# schematic.net
KiCad netlist of a schematic drawn in EAGLE
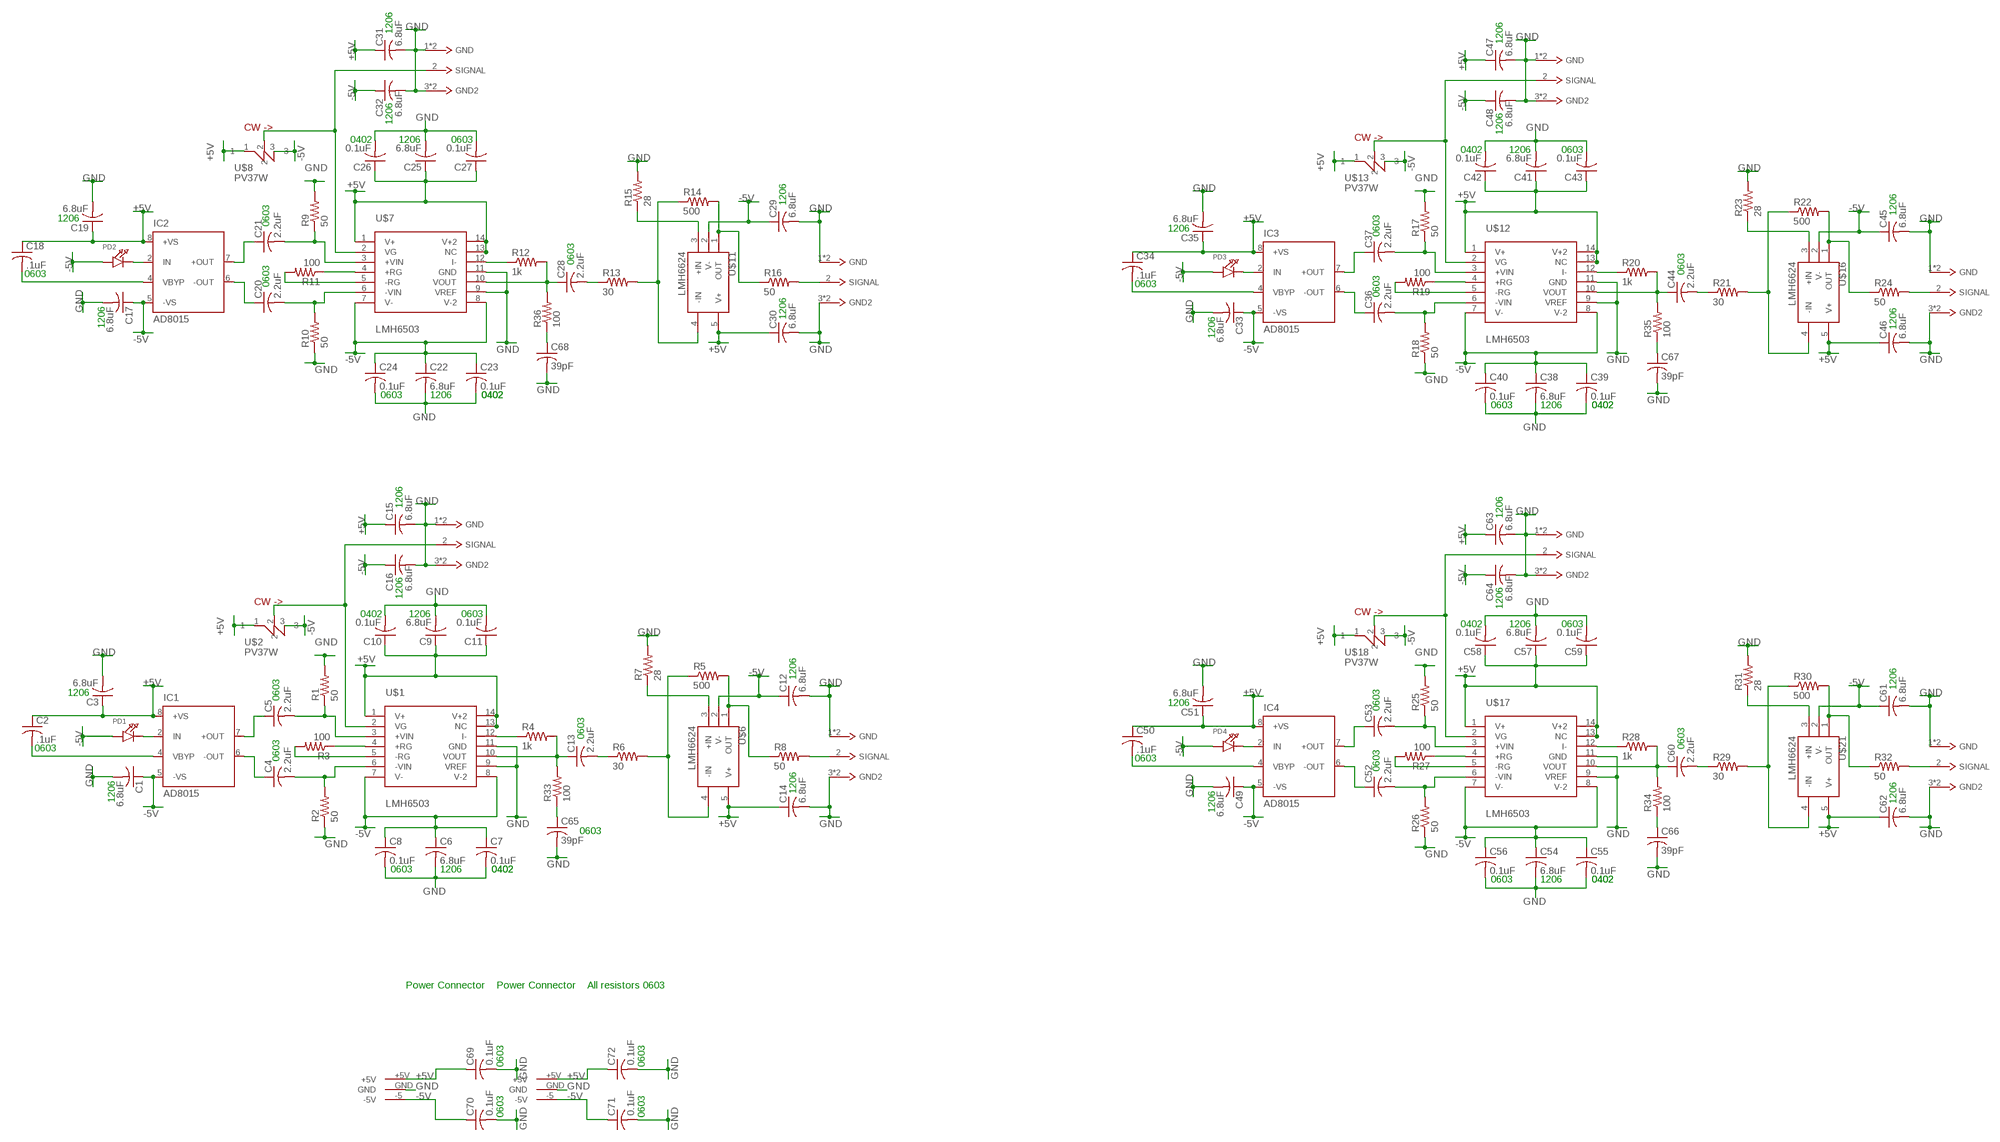
[diagram p0: schematic, sheet 1]

(export (version "E")
  (design (tool "Eeschema 10.0.6"))
  (components
    (comp (ref "C1")
      (value "6.8uF")
      (footprint "eagle-import:C1206")
      (libsource (lib "eagle-import") (part "C-USC1206"))
    )
    (comp (ref "C2")
      (value ".1uF")
      (footprint "eagle-import:C0603")
      (libsource (lib "eagle-import") (part "C-USC0603"))
    )
    (comp (ref "C3")
      (value "6.8uF")
      (footprint "eagle-import:C1206")
      (libsource (lib "eagle-import") (part "C-USC1206"))
    )
    (comp (ref "C4")
      (value "2.2uF")
      (footprint "eagle-import:C0603")
      (libsource (lib "eagle-import") (part "C-USC0603"))
    )
    (comp (ref "C5")
      (value "2.2uF")
      (footprint "eagle-import:C0603")
      (libsource (lib "eagle-import") (part "C-USC0603"))
    )
    (comp (ref "C6")
      (value "6.8uF")
      (footprint "eagle-import:C1206")
      (libsource (lib "eagle-import") (part "C-USC1206"))
    )
    (comp (ref "C7")
      (value "0.1uF")
      (footprint "eagle-import:C0402")
      (libsource (lib "eagle-import") (part "C-USC0402"))
    )
    (comp (ref "C8")
      (value "0.1uF")
      (footprint "eagle-import:C0603")
      (libsource (lib "eagle-import") (part "C-USC0603"))
    )
    (comp (ref "C9")
      (value "6.8uF")
      (footprint "eagle-import:C1206")
      (libsource (lib "eagle-import") (part "C-USC1206"))
    )
    (comp (ref "C10")
      (value "0.1uF")
      (footprint "eagle-import:C0402")
      (libsource (lib "eagle-import") (part "C-USC0402"))
    )
    (comp (ref "C11")
      (value "0.1uF")
      (footprint "eagle-import:C0603")
      (libsource (lib "eagle-import") (part "C-USC0603"))
    )
    (comp (ref "C12")
      (value "6.8uF")
      (footprint "eagle-import:C1206")
      (libsource (lib "eagle-import") (part "C-USC1206"))
    )
    (comp (ref "C13")
      (value "2.2uF")
      (footprint "eagle-import:C0603")
      (libsource (lib "eagle-import") (part "C-USC0603"))
    )
    (comp (ref "C14")
      (value "6.8uF")
      (footprint "eagle-import:C1206")
      (libsource (lib "eagle-import") (part "C-USC1206"))
    )
    (comp (ref "C15")
      (value "6.8uF")
      (footprint "eagle-import:C1206")
      (libsource (lib "eagle-import") (part "C-USC1206"))
    )
    (comp (ref "C16")
      (value "6.8uF")
      (footprint "eagle-import:C1206")
      (libsource (lib "eagle-import") (part "C-USC1206"))
    )
    (comp (ref "C17")
      (value "6.8uF")
      (footprint "eagle-import:C1206")
      (libsource (lib "eagle-import") (part "C-USC1206"))
    )
    (comp (ref "C18")
      (value ".1uF")
      (footprint "eagle-import:C0603")
      (libsource (lib "eagle-import") (part "C-USC0603"))
    )
    (comp (ref "C19")
      (value "6.8uF")
      (footprint "eagle-import:C1206")
      (libsource (lib "eagle-import") (part "C-USC1206"))
    )
    (comp (ref "C20")
      (value "2.2uF")
      (footprint "eagle-import:C0603")
      (libsource (lib "eagle-import") (part "C-USC0603"))
    )
    (comp (ref "C21")
      (value "2.2uF")
      (footprint "eagle-import:C0603")
      (libsource (lib "eagle-import") (part "C-USC0603"))
    )
    (comp (ref "C22")
      (value "6.8uF")
      (footprint "eagle-import:C1206")
      (libsource (lib "eagle-import") (part "C-USC1206"))
    )
    (comp (ref "C23")
      (value "0.1uF")
      (footprint "eagle-import:C0402")
      (libsource (lib "eagle-import") (part "C-USC0402"))
    )
    (comp (ref "C24")
      (value "0.1uF")
      (footprint "eagle-import:C0603")
      (libsource (lib "eagle-import") (part "C-USC0603"))
    )
    (comp (ref "C25")
      (value "6.8uF")
      (footprint "eagle-import:C1206")
      (libsource (lib "eagle-import") (part "C-USC1206"))
    )
    (comp (ref "C26")
      (value "0.1uF")
      (footprint "eagle-import:C0402")
      (libsource (lib "eagle-import") (part "C-USC0402"))
    )
    (comp (ref "C27")
      (value "0.1uF")
      (footprint "eagle-import:C0603")
      (libsource (lib "eagle-import") (part "C-USC0603"))
    )
    (comp (ref "C28")
      (value "2.2uF")
      (footprint "eagle-import:C0603")
      (libsource (lib "eagle-import") (part "C-USC0603"))
    )
    (comp (ref "C29")
      (value "6.8uF")
      (footprint "eagle-import:C1206")
      (libsource (lib "eagle-import") (part "C-USC1206"))
    )
    (comp (ref "C30")
      (value "6.8uF")
      (footprint "eagle-import:C1206")
      (libsource (lib "eagle-import") (part "C-USC1206"))
    )
    (comp (ref "C31")
      (value "6.8uF")
      (footprint "eagle-import:C1206")
      (libsource (lib "eagle-import") (part "C-USC1206"))
    )
    (comp (ref "C32")
      (value "6.8uF")
      (footprint "eagle-import:C1206")
      (libsource (lib "eagle-import") (part "C-USC1206"))
    )
    (comp (ref "C33")
      (value "6.8uF")
      (footprint "eagle-import:C1206")
      (libsource (lib "eagle-import") (part "C-USC1206"))
    )
    (comp (ref "C34")
      (value ".1uF")
      (footprint "eagle-import:C0603")
      (libsource (lib "eagle-import") (part "C-USC0603"))
    )
    (comp (ref "C35")
      (value "6.8uF")
      (footprint "eagle-import:C1206")
      (libsource (lib "eagle-import") (part "C-USC1206"))
    )
    (comp (ref "C36")
      (value "2.2uF")
      (footprint "eagle-import:C0603")
      (libsource (lib "eagle-import") (part "C-USC0603"))
    )
    (comp (ref "C37")
      (value "2.2uF")
      (footprint "eagle-import:C0603")
      (libsource (lib "eagle-import") (part "C-USC0603"))
    )
    (comp (ref "C38")
      (value "6.8uF")
      (footprint "eagle-import:C1206")
      (libsource (lib "eagle-import") (part "C-USC1206"))
    )
    (comp (ref "C39")
      (value "0.1uF")
      (footprint "eagle-import:C0402")
      (libsource (lib "eagle-import") (part "C-USC0402"))
    )
    (comp (ref "C40")
      (value "0.1uF")
      (footprint "eagle-import:C0603")
      (libsource (lib "eagle-import") (part "C-USC0603"))
    )
    (comp (ref "C41")
      (value "6.8uF")
      (footprint "eagle-import:C1206")
      (libsource (lib "eagle-import") (part "C-USC1206"))
    )
    (comp (ref "C42")
      (value "0.1uF")
      (footprint "eagle-import:C0402")
      (libsource (lib "eagle-import") (part "C-USC0402"))
    )
    (comp (ref "C43")
      (value "0.1uF")
      (footprint "eagle-import:C0603")
      (libsource (lib "eagle-import") (part "C-USC0603"))
    )
    (comp (ref "C44")
      (value "2.2uF")
      (footprint "eagle-import:C0603")
      (libsource (lib "eagle-import") (part "C-USC0603"))
    )
    (comp (ref "C45")
      (value "6.8uF")
      (footprint "eagle-import:C1206")
      (libsource (lib "eagle-import") (part "C-USC1206"))
    )
    (comp (ref "C46")
      (value "6.8uF")
      (footprint "eagle-import:C1206")
      (libsource (lib "eagle-import") (part "C-USC1206"))
    )
    (comp (ref "C47")
      (value "6.8uF")
      (footprint "eagle-import:C1206")
      (libsource (lib "eagle-import") (part "C-USC1206"))
    )
    (comp (ref "C48")
      (value "6.8uF")
      (footprint "eagle-import:C1206")
      (libsource (lib "eagle-import") (part "C-USC1206"))
    )
    (comp (ref "C49")
      (value "6.8uF")
      (footprint "eagle-import:C1206")
      (libsource (lib "eagle-import") (part "C-USC1206"))
    )
    (comp (ref "C50")
      (value ".1uF")
      (footprint "eagle-import:C0603")
      (libsource (lib "eagle-import") (part "C-USC0603"))
    )
    (comp (ref "C51")
      (value "6.8uF")
      (footprint "eagle-import:C1206")
      (libsource (lib "eagle-import") (part "C-USC1206"))
    )
    (comp (ref "C52")
      (value "2.2uF")
      (footprint "eagle-import:C0603")
      (libsource (lib "eagle-import") (part "C-USC0603"))
    )
    (comp (ref "C53")
      (value "2.2uF")
      (footprint "eagle-import:C0603")
      (libsource (lib "eagle-import") (part "C-USC0603"))
    )
    (comp (ref "C54")
      (value "6.8uF")
      (footprint "eagle-import:C1206")
      (libsource (lib "eagle-import") (part "C-USC1206"))
    )
    (comp (ref "C55")
      (value "0.1uF")
      (footprint "eagle-import:C0402")
      (libsource (lib "eagle-import") (part "C-USC0402"))
    )
    (comp (ref "C56")
      (value "0.1uF")
      (footprint "eagle-import:C0603")
      (libsource (lib "eagle-import") (part "C-USC0603"))
    )
    (comp (ref "C57")
      (value "6.8uF")
      (footprint "eagle-import:C1206")
      (libsource (lib "eagle-import") (part "C-USC1206"))
    )
    (comp (ref "C58")
      (value "0.1uF")
      (footprint "eagle-import:C0402")
      (libsource (lib "eagle-import") (part "C-USC0402"))
    )
    (comp (ref "C59")
      (value "0.1uF")
      (footprint "eagle-import:C0603")
      (libsource (lib "eagle-import") (part "C-USC0603"))
    )
    (comp (ref "C60")
      (value "2.2uF")
      (footprint "eagle-import:C0603")
      (libsource (lib "eagle-import") (part "C-USC0603"))
    )
    (comp (ref "C61")
      (value "6.8uF")
      (footprint "eagle-import:C1206")
      (libsource (lib "eagle-import") (part "C-USC1206"))
    )
    (comp (ref "C62")
      (value "6.8uF")
      (footprint "eagle-import:C1206")
      (libsource (lib "eagle-import") (part "C-USC1206"))
    )
    (comp (ref "C63")
      (value "6.8uF")
      (footprint "eagle-import:C1206")
      (libsource (lib "eagle-import") (part "C-USC1206"))
    )
    (comp (ref "C64")
      (value "6.8uF")
      (footprint "eagle-import:C1206")
      (libsource (lib "eagle-import") (part "C-USC1206"))
    )
    (comp (ref "C65")
      (value "39pF")
      (footprint "eagle-import:C0603")
      (libsource (lib "eagle-import") (part "C-USC0603"))
    )
    (comp (ref "C66")
      (value "39pF")
      (footprint "eagle-import:C0603")
      (libsource (lib "eagle-import") (part "C-USC0603"))
    )
    (comp (ref "C67")
      (value "39pF")
      (footprint "eagle-import:C0603")
      (libsource (lib "eagle-import") (part "C-USC0603"))
    )
    (comp (ref "C68")
      (value "39pF")
      (footprint "eagle-import:C0603")
      (libsource (lib "eagle-import") (part "C-USC0603"))
    )
    (comp (ref "C69")
      (value "0.1uF")
      (footprint "eagle-import:C0402")
      (libsource (lib "eagle-import") (part "C-USC0402"))
    )
    (comp (ref "C70")
      (value "0.1uF")
      (footprint "eagle-import:C0402")
      (libsource (lib "eagle-import") (part "C-USC0402"))
    )
    (comp (ref "C71")
      (value "0.1uF")
      (footprint "eagle-import:C0402")
      (libsource (lib "eagle-import") (part "C-USC0402"))
    )
    (comp (ref "C72")
      (value "0.1uF")
      (footprint "eagle-import:C0402")
      (libsource (lib "eagle-import") (part "C-USC0402"))
    )
    (comp (ref "IC1")
      (value "AD8015")
      (footprint "eagle-import:SO8")
      (fields (field (name "MPN") "AD8015ARZ"))
      (libsource (lib "eagle-import") (part "AD8015"))
    )
    (comp (ref "IC2")
      (value "AD8015")
      (footprint "eagle-import:SO8")
      (fields (field (name "MPN") "AD8015ARZ"))
      (libsource (lib "eagle-import") (part "AD8015"))
    )
    (comp (ref "IC3")
      (value "AD8015")
      (footprint "eagle-import:SO8")
      (fields (field (name "MPN") "AD8015ARZ"))
      (libsource (lib "eagle-import") (part "AD8015"))
    )
    (comp (ref "IC4")
      (value "AD8015")
      (footprint "eagle-import:SO8")
      (fields (field (name "MPN") "AD8015ARZ"))
      (libsource (lib "eagle-import") (part "AD8015"))
    )
    (comp (ref "PD1")
      (value "LED1206")
      (footprint "eagle-import:CHIPLED_1206")
      (libsource (lib "eagle-import") (part "LED1206"))
    )
    (comp (ref "PD2")
      (value "LED1206")
      (footprint "eagle-import:CHIPLED_1206")
      (libsource (lib "eagle-import") (part "LED1206"))
    )
    (comp (ref "PD3")
      (value "LED1206")
      (footprint "eagle-import:CHIPLED_1206")
      (libsource (lib "eagle-import") (part "LED1206"))
    )
    (comp (ref "PD4")
      (value "LED1206")
      (footprint "eagle-import:CHIPLED_1206")
      (libsource (lib "eagle-import") (part "LED1206"))
    )
    (comp (ref "R1")
      (value "50")
      (footprint "eagle-import:R0603")
      (libsource (lib "eagle-import") (part "R-US_R0603"))
    )
    (comp (ref "R2")
      (value "50")
      (footprint "eagle-import:R0603")
      (libsource (lib "eagle-import") (part "R-US_R0603"))
    )
    (comp (ref "R3")
      (value "100")
      (footprint "eagle-import:R0603")
      (libsource (lib "eagle-import") (part "R-US_R0603"))
    )
    (comp (ref "R4")
      (value "1k")
      (footprint "eagle-import:R0603")
      (libsource (lib "eagle-import") (part "R-US_R0603"))
    )
    (comp (ref "R5")
      (value "500")
      (footprint "eagle-import:R0603")
      (libsource (lib "eagle-import") (part "R-US_R0603"))
    )
    (comp (ref "R6")
      (value "30")
      (footprint "eagle-import:R0603")
      (libsource (lib "eagle-import") (part "R-US_R0603"))
    )
    (comp (ref "R7")
      (value "28")
      (footprint "eagle-import:R0603")
      (libsource (lib "eagle-import") (part "R-US_R0603"))
    )
    (comp (ref "R8")
      (value "50")
      (footprint "eagle-import:R0603")
      (libsource (lib "eagle-import") (part "R-US_R0603"))
    )
    (comp (ref "R9")
      (value "50")
      (footprint "eagle-import:R0603")
      (libsource (lib "eagle-import") (part "R-US_R0603"))
    )
    (comp (ref "R10")
      (value "50")
      (footprint "eagle-import:R0603")
      (libsource (lib "eagle-import") (part "R-US_R0603"))
    )
    (comp (ref "R11")
      (value "100")
      (footprint "eagle-import:R0603")
      (libsource (lib "eagle-import") (part "R-US_R0603"))
    )
    (comp (ref "R12")
      (value "1k")
      (footprint "eagle-import:R0603")
      (libsource (lib "eagle-import") (part "R-US_R0603"))
    )
    (comp (ref "R13")
      (value "30")
      (footprint "eagle-import:R0603")
      (libsource (lib "eagle-import") (part "R-US_R0603"))
    )
    (comp (ref "R14")
      (value "500")
      (footprint "eagle-import:R0603")
      (libsource (lib "eagle-import") (part "R-US_R0603"))
    )
    (comp (ref "R15")
      (value "28")
      (footprint "eagle-import:R0603")
      (libsource (lib "eagle-import") (part "R-US_R0603"))
    )
    (comp (ref "R16")
      (value "50")
      (footprint "eagle-import:R0603")
      (libsource (lib "eagle-import") (part "R-US_R0603"))
    )
    (comp (ref "R17")
      (value "50")
      (footprint "eagle-import:R0603")
      (libsource (lib "eagle-import") (part "R-US_R0603"))
    )
    (comp (ref "R18")
      (value "50")
      (footprint "eagle-import:R0603")
      (libsource (lib "eagle-import") (part "R-US_R0603"))
    )
    (comp (ref "R19")
      (value "100")
      (footprint "eagle-import:R0603")
      (libsource (lib "eagle-import") (part "R-US_R0603"))
    )
    (comp (ref "R20")
      (value "1k")
      (footprint "eagle-import:R0603")
      (libsource (lib "eagle-import") (part "R-US_R0603"))
    )
    (comp (ref "R21")
      (value "30")
      (footprint "eagle-import:R0603")
      (libsource (lib "eagle-import") (part "R-US_R0603"))
    )
    (comp (ref "R22")
      (value "500")
      (footprint "eagle-import:R0603")
      (libsource (lib "eagle-import") (part "R-US_R0603"))
    )
    (comp (ref "R23")
      (value "28")
      (footprint "eagle-import:R0603")
      (libsource (lib "eagle-import") (part "R-US_R0603"))
    )
    (comp (ref "R24")
      (value "50")
      (footprint "eagle-import:R0603")
      (libsource (lib "eagle-import") (part "R-US_R0603"))
    )
    (comp (ref "R25")
      (value "50")
      (footprint "eagle-import:R0603")
      (libsource (lib "eagle-import") (part "R-US_R0603"))
    )
    (comp (ref "R26")
      (value "50")
      (footprint "eagle-import:R0603")
      (libsource (lib "eagle-import") (part "R-US_R0603"))
    )
    (comp (ref "R27")
      (value "100")
      (footprint "eagle-import:R0603")
      (libsource (lib "eagle-import") (part "R-US_R0603"))
    )
    (comp (ref "R28")
      (value "1k")
      (footprint "eagle-import:R0603")
      (libsource (lib "eagle-import") (part "R-US_R0603"))
    )
    (comp (ref "R29")
      (value "30")
      (footprint "eagle-import:R0603")
      (libsource (lib "eagle-import") (part "R-US_R0603"))
    )
    (comp (ref "R30")
      (value "500")
      (footprint "eagle-import:R0603")
      (libsource (lib "eagle-import") (part "R-US_R0603"))
    )
    (comp (ref "R31")
      (value "28")
      (footprint "eagle-import:R0603")
      (libsource (lib "eagle-import") (part "R-US_R0603"))
    )
    (comp (ref "R32")
      (value "50")
      (footprint "eagle-import:R0603")
      (libsource (lib "eagle-import") (part "R-US_R0603"))
    )
    (comp (ref "R33")
      (value "100")
      (footprint "eagle-import:R0603")
      (libsource (lib "eagle-import") (part "R-US_R0603"))
    )
    (comp (ref "R34")
      (value "100")
      (footprint "eagle-import:R0603")
      (libsource (lib "eagle-import") (part "R-US_R0603"))
    )
    (comp (ref "R35")
      (value "100")
      (footprint "eagle-import:R0603")
      (libsource (lib "eagle-import") (part "R-US_R0603"))
    )
    (comp (ref "R36")
      (value "100")
      (footprint "eagle-import:R0603")
      (libsource (lib "eagle-import") (part "R-US_R0603"))
    )
    (comp (ref "U$1")
      (value "LMH6503")
      (footprint "eagle-import:SOIC14")
      (libsource (lib "eagle-import") (part "LMH6503"))
    )
    (comp (ref "U$2")
      (value "PV37W")
      (footprint "eagle-import:PV37W")
      (libsource (lib "eagle-import") (part "PV37W"))
    )
    (comp (ref "U$3")
      (value "DIVERSITYPWR")
      (footprint "eagle-import:DIVERSITYPOWER")
      (libsource (lib "eagle-import") (part "DIVERSITYPWR"))
    )
    (comp (ref "U$4")
      (value "BNCCONN")
      (footprint "eagle-import:BNCPADS")
      (libsource (lib "eagle-import") (part "BNCCONN"))
    )
    (comp (ref "U$5")
      (value "BNCCONN")
      (footprint "eagle-import:BNCPADS")
      (libsource (lib "eagle-import") (part "BNCCONN"))
    )
    (comp (ref "U$6")
      (value "LMH6624")
      (footprint "eagle-import:SOT-23")
      (libsource (lib "eagle-import") (part "LMH6624"))
    )
    (comp (ref "U$7")
      (value "LMH6503")
      (footprint "eagle-import:SOIC14")
      (libsource (lib "eagle-import") (part "LMH6503"))
    )
    (comp (ref "U$8")
      (value "PV37W")
      (footprint "eagle-import:PV37W")
      (libsource (lib "eagle-import") (part "PV37W"))
    )
    (comp (ref "U$9")
      (value "BNCCONN")
      (footprint "eagle-import:BNCPADS")
      (libsource (lib "eagle-import") (part "BNCCONN"))
    )
    (comp (ref "U$10")
      (value "BNCCONN")
      (footprint "eagle-import:BNCPADS")
      (libsource (lib "eagle-import") (part "BNCCONN"))
    )
    (comp (ref "U$11")
      (value "LMH6624")
      (footprint "eagle-import:SOT-23")
      (libsource (lib "eagle-import") (part "LMH6624"))
    )
    (comp (ref "U$12")
      (value "LMH6503")
      (footprint "eagle-import:SOIC14")
      (libsource (lib "eagle-import") (part "LMH6503"))
    )
    (comp (ref "U$13")
      (value "PV37W")
      (footprint "eagle-import:PV37W")
      (libsource (lib "eagle-import") (part "PV37W"))
    )
    (comp (ref "U$14")
      (value "BNCCONN")
      (footprint "eagle-import:BNCPADS")
      (libsource (lib "eagle-import") (part "BNCCONN"))
    )
    (comp (ref "U$15")
      (value "BNCCONN")
      (footprint "eagle-import:BNCPADS")
      (libsource (lib "eagle-import") (part "BNCCONN"))
    )
    (comp (ref "U$16")
      (value "LMH6624")
      (footprint "eagle-import:SOT-23")
      (libsource (lib "eagle-import") (part "LMH6624"))
    )
    (comp (ref "U$17")
      (value "LMH6503")
      (footprint "eagle-import:SOIC14")
      (libsource (lib "eagle-import") (part "LMH6503"))
    )
    (comp (ref "U$18")
      (value "PV37W")
      (footprint "eagle-import:PV37W")
      (libsource (lib "eagle-import") (part "PV37W"))
    )
    (comp (ref "U$19")
      (value "BNCCONN")
      (footprint "eagle-import:BNCPADS")
      (libsource (lib "eagle-import") (part "BNCCONN"))
    )
    (comp (ref "U$20")
      (value "BNCCONN")
      (footprint "eagle-import:BNCPADS")
      (libsource (lib "eagle-import") (part "BNCCONN"))
    )
    (comp (ref "U$21")
      (value "LMH6624")
      (footprint "eagle-import:SOT-23")
      (libsource (lib "eagle-import") (part "LMH6624"))
    )
    (comp (ref "U$22")
      (value "DIVERSITYPWR")
      (footprint "eagle-import:DIVERSITYPOWER")
      (libsource (lib "eagle-import") (part "DIVERSITYPWR"))
    )
  )
  (nets
    (net (code "1") (name "/+5V") (class "Default")
      (node (ref "C10") (pin "1") (pinfunction "1_1") (pintype "passive"))
      (node (ref "C11") (pin "1") (pinfunction "1_1") (pintype "passive"))
      (node (ref "C14") (pin "1") (pinfunction "1_1") (pintype "passive"))
      (node (ref "C15") (pin "1") (pinfunction "1_1") (pintype "passive"))
      (node (ref "C18") (pin "1") (pinfunction "1_1") (pintype "passive"))
      (node (ref "C19") (pin "1") (pinfunction "1_1") (pintype "passive"))
      (node (ref "C2") (pin "1") (pinfunction "1_1") (pintype "passive"))
      (node (ref "C25") (pin "1") (pinfunction "1_1") (pintype "passive"))
      (node (ref "C26") (pin "1") (pinfunction "1_1") (pintype "passive"))
      (node (ref "C27") (pin "1") (pinfunction "1_1") (pintype "passive"))
      (node (ref "C3") (pin "1") (pinfunction "1_1") (pintype "passive"))
      (node (ref "C30") (pin "1") (pinfunction "1_1") (pintype "passive"))
      (node (ref "C31") (pin "1") (pinfunction "1_1") (pintype "passive"))
      (node (ref "C34") (pin "1") (pinfunction "1_1") (pintype "passive"))
      (node (ref "C35") (pin "1") (pinfunction "1_1") (pintype "passive"))
      (node (ref "C41") (pin "1") (pinfunction "1_1") (pintype "passive"))
      (node (ref "C42") (pin "1") (pinfunction "1_1") (pintype "passive"))
      (node (ref "C43") (pin "1") (pinfunction "1_1") (pintype "passive"))
      (node (ref "C46") (pin "1") (pinfunction "1_1") (pintype "passive"))
      (node (ref "C47") (pin "1") (pinfunction "1_1") (pintype "passive"))
      (node (ref "C50") (pin "1") (pinfunction "1_1") (pintype "passive"))
      (node (ref "C51") (pin "1") (pinfunction "1_1") (pintype "passive"))
      (node (ref "C57") (pin "1") (pinfunction "1_1") (pintype "passive"))
      (node (ref "C58") (pin "1") (pinfunction "1_1") (pintype "passive"))
      (node (ref "C59") (pin "1") (pinfunction "1_1") (pintype "passive"))
      (node (ref "C62") (pin "1") (pinfunction "1_1") (pintype "passive"))
      (node (ref "C63") (pin "1") (pinfunction "1_1") (pintype "passive"))
      (node (ref "C69") (pin "1") (pinfunction "1_1") (pintype "passive"))
      (node (ref "C72") (pin "1") (pinfunction "1_1") (pintype "passive"))
      (node (ref "C9") (pin "1") (pinfunction "1_1") (pintype "passive"))
      (node (ref "IC1") (pin "8") (pinfunction "+VS_8") (pintype "input"))
      (node (ref "IC2") (pin "8") (pinfunction "+VS_8") (pintype "input"))
      (node (ref "IC3") (pin "8") (pinfunction "+VS_8") (pintype "input"))
      (node (ref "IC4") (pin "8") (pinfunction "+VS_8") (pintype "input"))
      (node (ref "U$1") (pin "1") (pinfunction "V+_1") (pintype "bidirectional"))
      (node (ref "U$1") (pin "13") (pinfunction "NC_13") (pintype "bidirectional"))
      (node (ref "U$1") (pin "14") (pinfunction "V+2_14") (pintype "bidirectional"))
      (node (ref "U$11") (pin "5") (pinfunction "V+_5") (pintype "bidirectional"))
      (node (ref "U$12") (pin "1") (pinfunction "V+_1") (pintype "bidirectional"))
      (node (ref "U$12") (pin "13") (pinfunction "NC_13") (pintype "bidirectional"))
      (node (ref "U$12") (pin "14") (pinfunction "V+2_14") (pintype "bidirectional"))
      (node (ref "U$13") (pin "1") (pinfunction "1_1") (pintype "bidirectional"))
      (node (ref "U$16") (pin "5") (pinfunction "V+_5") (pintype "bidirectional"))
      (node (ref "U$17") (pin "1") (pinfunction "V+_1") (pintype "bidirectional"))
      (node (ref "U$17") (pin "13") (pinfunction "NC_13") (pintype "bidirectional"))
      (node (ref "U$17") (pin "14") (pinfunction "V+2_14") (pintype "bidirectional"))
      (node (ref "U$18") (pin "1") (pinfunction "1_1") (pintype "bidirectional"))
      (node (ref "U$2") (pin "1") (pinfunction "1_1") (pintype "bidirectional"))
      (node (ref "U$21") (pin "5") (pinfunction "V+_5") (pintype "bidirectional"))
      (node (ref "U$22") (pin "+5V") (pinfunction "+5V_+5V") (pintype "bidirectional"))
      (node (ref "U$3") (pin "+5V") (pinfunction "+5V_+5V") (pintype "bidirectional"))
      (node (ref "U$6") (pin "5") (pinfunction "V+_5") (pintype "bidirectional"))
      (node (ref "U$7") (pin "1") (pinfunction "V+_1") (pintype "bidirectional"))
      (node (ref "U$7") (pin "13") (pinfunction "NC_13") (pintype "bidirectional"))
      (node (ref "U$7") (pin "14") (pinfunction "V+2_14") (pintype "bidirectional"))
      (node (ref "U$8") (pin "1") (pinfunction "1_1") (pintype "bidirectional"))
    )
    (net (code "2") (name "/-5V") (class "Default")
      (node (ref "C1") (pin "1") (pinfunction "1_1") (pintype "passive"))
      (node (ref "C12") (pin "1") (pinfunction "1_1") (pintype "passive"))
      (node (ref "C16") (pin "1") (pinfunction "1_1") (pintype "passive"))
      (node (ref "C17") (pin "1") (pinfunction "1_1") (pintype "passive"))
      (node (ref "C22") (pin "1") (pinfunction "1_1") (pintype "passive"))
      (node (ref "C23") (pin "1") (pinfunction "1_1") (pintype "passive"))
      (node (ref "C24") (pin "1") (pinfunction "1_1") (pintype "passive"))
      (node (ref "C29") (pin "1") (pinfunction "1_1") (pintype "passive"))
      (node (ref "C32") (pin "1") (pinfunction "1_1") (pintype "passive"))
      (node (ref "C33") (pin "1") (pinfunction "1_1") (pintype "passive"))
      (node (ref "C38") (pin "1") (pinfunction "1_1") (pintype "passive"))
      (node (ref "C39") (pin "1") (pinfunction "1_1") (pintype "passive"))
      (node (ref "C40") (pin "1") (pinfunction "1_1") (pintype "passive"))
      (node (ref "C45") (pin "1") (pinfunction "1_1") (pintype "passive"))
      (node (ref "C48") (pin "1") (pinfunction "1_1") (pintype "passive"))
      (node (ref "C49") (pin "1") (pinfunction "1_1") (pintype "passive"))
      (node (ref "C54") (pin "1") (pinfunction "1_1") (pintype "passive"))
      (node (ref "C55") (pin "1") (pinfunction "1_1") (pintype "passive"))
      (node (ref "C56") (pin "1") (pinfunction "1_1") (pintype "passive"))
      (node (ref "C6") (pin "1") (pinfunction "1_1") (pintype "passive"))
      (node (ref "C61") (pin "1") (pinfunction "1_1") (pintype "passive"))
      (node (ref "C64") (pin "1") (pinfunction "1_1") (pintype "passive"))
      (node (ref "C7") (pin "1") (pinfunction "1_1") (pintype "passive"))
      (node (ref "C70") (pin "1") (pinfunction "1_1") (pintype "passive"))
      (node (ref "C71") (pin "1") (pinfunction "1_1") (pintype "passive"))
      (node (ref "C8") (pin "1") (pinfunction "1_1") (pintype "passive"))
      (node (ref "IC1") (pin "5") (pinfunction "-VS_5") (pintype "input"))
      (node (ref "IC2") (pin "5") (pinfunction "-VS_5") (pintype "input"))
      (node (ref "IC3") (pin "5") (pinfunction "-VS_5") (pintype "input"))
      (node (ref "IC4") (pin "5") (pinfunction "-VS_5") (pintype "input"))
      (node (ref "PD1") (pin "A") (pinfunction "A_A") (pintype "passive"))
      (node (ref "PD2") (pin "A") (pinfunction "A_A") (pintype "passive"))
      (node (ref "PD3") (pin "A") (pinfunction "A_A") (pintype "passive"))
      (node (ref "PD4") (pin "A") (pinfunction "A_A") (pintype "passive"))
      (node (ref "U$1") (pin "7") (pinfunction "V-_7") (pintype "bidirectional"))
      (node (ref "U$1") (pin "8") (pinfunction "V-2_8") (pintype "bidirectional"))
      (node (ref "U$11") (pin "2") (pinfunction "V-_2") (pintype "bidirectional"))
      (node (ref "U$12") (pin "7") (pinfunction "V-_7") (pintype "bidirectional"))
      (node (ref "U$12") (pin "8") (pinfunction "V-2_8") (pintype "bidirectional"))
      (node (ref "U$13") (pin "3") (pinfunction "3_3") (pintype "bidirectional"))
      (node (ref "U$16") (pin "2") (pinfunction "V-_2") (pintype "bidirectional"))
      (node (ref "U$17") (pin "7") (pinfunction "V-_7") (pintype "bidirectional"))
      (node (ref "U$17") (pin "8") (pinfunction "V-2_8") (pintype "bidirectional"))
      (node (ref "U$18") (pin "3") (pinfunction "3_3") (pintype "bidirectional"))
      (node (ref "U$2") (pin "3") (pinfunction "3_3") (pintype "bidirectional"))
      (node (ref "U$21") (pin "2") (pinfunction "V-_2") (pintype "bidirectional"))
      (node (ref "U$22") (pin "-5") (pinfunction "-5V_-5") (pintype "bidirectional"))
      (node (ref "U$3") (pin "-5") (pinfunction "-5V_-5") (pintype "bidirectional"))
      (node (ref "U$6") (pin "2") (pinfunction "V-_2") (pintype "bidirectional"))
      (node (ref "U$7") (pin "7") (pinfunction "V-_7") (pintype "bidirectional"))
      (node (ref "U$7") (pin "8") (pinfunction "V-2_8") (pintype "bidirectional"))
      (node (ref "U$8") (pin "3") (pinfunction "3_3") (pintype "bidirectional"))
    )
    (net (code "3") (name "/GND") (class "Default")
      (node (ref "C1") (pin "2") (pinfunction "2_2") (pintype "passive"))
      (node (ref "C10") (pin "2") (pinfunction "2_2") (pintype "passive"))
      (node (ref "C11") (pin "2") (pinfunction "2_2") (pintype "passive"))
      (node (ref "C12") (pin "2") (pinfunction "2_2") (pintype "passive"))
      (node (ref "C14") (pin "2") (pinfunction "2_2") (pintype "passive"))
      (node (ref "C15") (pin "2") (pinfunction "2_2") (pintype "passive"))
      (node (ref "C16") (pin "2") (pinfunction "2_2") (pintype "passive"))
      (node (ref "C17") (pin "2") (pinfunction "2_2") (pintype "passive"))
      (node (ref "C19") (pin "2") (pinfunction "2_2") (pintype "passive"))
      (node (ref "C22") (pin "2") (pinfunction "2_2") (pintype "passive"))
      (node (ref "C23") (pin "2") (pinfunction "2_2") (pintype "passive"))
      (node (ref "C24") (pin "2") (pinfunction "2_2") (pintype "passive"))
      (node (ref "C25") (pin "2") (pinfunction "2_2") (pintype "passive"))
      (node (ref "C26") (pin "2") (pinfunction "2_2") (pintype "passive"))
      (node (ref "C27") (pin "2") (pinfunction "2_2") (pintype "passive"))
      (node (ref "C29") (pin "2") (pinfunction "2_2") (pintype "passive"))
      (node (ref "C3") (pin "2") (pinfunction "2_2") (pintype "passive"))
      (node (ref "C30") (pin "2") (pinfunction "2_2") (pintype "passive"))
      (node (ref "C31") (pin "2") (pinfunction "2_2") (pintype "passive"))
      (node (ref "C32") (pin "2") (pinfunction "2_2") (pintype "passive"))
      (node (ref "C33") (pin "2") (pinfunction "2_2") (pintype "passive"))
      (node (ref "C35") (pin "2") (pinfunction "2_2") (pintype "passive"))
      (node (ref "C38") (pin "2") (pinfunction "2_2") (pintype "passive"))
      (node (ref "C39") (pin "2") (pinfunction "2_2") (pintype "passive"))
      (node (ref "C40") (pin "2") (pinfunction "2_2") (pintype "passive"))
      (node (ref "C41") (pin "2") (pinfunction "2_2") (pintype "passive"))
      (node (ref "C42") (pin "2") (pinfunction "2_2") (pintype "passive"))
      (node (ref "C43") (pin "2") (pinfunction "2_2") (pintype "passive"))
      (node (ref "C45") (pin "2") (pinfunction "2_2") (pintype "passive"))
      (node (ref "C46") (pin "2") (pinfunction "2_2") (pintype "passive"))
      (node (ref "C47") (pin "2") (pinfunction "2_2") (pintype "passive"))
      (node (ref "C48") (pin "2") (pinfunction "2_2") (pintype "passive"))
      (node (ref "C49") (pin "2") (pinfunction "2_2") (pintype "passive"))
      (node (ref "C51") (pin "2") (pinfunction "2_2") (pintype "passive"))
      (node (ref "C54") (pin "2") (pinfunction "2_2") (pintype "passive"))
      (node (ref "C55") (pin "2") (pinfunction "2_2") (pintype "passive"))
      (node (ref "C56") (pin "2") (pinfunction "2_2") (pintype "passive"))
      (node (ref "C57") (pin "2") (pinfunction "2_2") (pintype "passive"))
      (node (ref "C58") (pin "2") (pinfunction "2_2") (pintype "passive"))
      (node (ref "C59") (pin "2") (pinfunction "2_2") (pintype "passive"))
      (node (ref "C6") (pin "2") (pinfunction "2_2") (pintype "passive"))
      (node (ref "C61") (pin "2") (pinfunction "2_2") (pintype "passive"))
      (node (ref "C62") (pin "2") (pinfunction "2_2") (pintype "passive"))
      (node (ref "C63") (pin "2") (pinfunction "2_2") (pintype "passive"))
      (node (ref "C64") (pin "2") (pinfunction "2_2") (pintype "passive"))
      (node (ref "C65") (pin "2") (pinfunction "2_2") (pintype "passive"))
      (node (ref "C66") (pin "2") (pinfunction "2_2") (pintype "passive"))
      (node (ref "C67") (pin "2") (pinfunction "2_2") (pintype "passive"))
      (node (ref "C68") (pin "2") (pinfunction "2_2") (pintype "passive"))
      (node (ref "C69") (pin "2") (pinfunction "2_2") (pintype "passive"))
      (node (ref "C7") (pin "2") (pinfunction "2_2") (pintype "passive"))
      (node (ref "C70") (pin "2") (pinfunction "2_2") (pintype "passive"))
      (node (ref "C71") (pin "2") (pinfunction "2_2") (pintype "passive"))
      (node (ref "C72") (pin "2") (pinfunction "2_2") (pintype "passive"))
      (node (ref "C8") (pin "2") (pinfunction "2_2") (pintype "passive"))
      (node (ref "C9") (pin "2") (pinfunction "2_2") (pintype "passive"))
      (node (ref "R1") (pin "2") (pinfunction "2_2") (pintype "passive"))
      (node (ref "R10") (pin "1") (pinfunction "1_1") (pintype "passive"))
      (node (ref "R15") (pin "2") (pinfunction "2_2") (pintype "passive"))
      (node (ref "R17") (pin "2") (pinfunction "2_2") (pintype "passive"))
      (node (ref "R18") (pin "1") (pinfunction "1_1") (pintype "passive"))
      (node (ref "R2") (pin "1") (pinfunction "1_1") (pintype "passive"))
      (node (ref "R23") (pin "2") (pinfunction "2_2") (pintype "passive"))
      (node (ref "R25") (pin "2") (pinfunction "2_2") (pintype "passive"))
      (node (ref "R26") (pin "1") (pinfunction "1_1") (pintype "passive"))
      (node (ref "R31") (pin "2") (pinfunction "2_2") (pintype "passive"))
      (node (ref "R7") (pin "2") (pinfunction "2_2") (pintype "passive"))
      (node (ref "R9") (pin "2") (pinfunction "2_2") (pintype "passive"))
      (node (ref "U$1") (pin "11") (pinfunction "GND_11") (pintype "bidirectional"))
      (node (ref "U$1") (pin "9") (pinfunction "VREF_9") (pintype "bidirectional"))
      (node (ref "U$10") (pin "1") (pinfunction "GND_1") (pintype "bidirectional"))
      (node (ref "U$10") (pin "3") (pinfunction "GND2_3") (pintype "bidirectional"))
      (node (ref "U$10") (pin "4") (pinfunction "GND_4") (pintype "bidirectional"))
      (node (ref "U$10") (pin "5") (pinfunction "GND2_5") (pintype "bidirectional"))
      (node (ref "U$12") (pin "11") (pinfunction "GND_11") (pintype "bidirectional"))
      (node (ref "U$12") (pin "9") (pinfunction "VREF_9") (pintype "bidirectional"))
      (node (ref "U$14") (pin "1") (pinfunction "GND_1") (pintype "bidirectional"))
      (node (ref "U$14") (pin "3") (pinfunction "GND2_3") (pintype "bidirectional"))
      (node (ref "U$14") (pin "4") (pinfunction "GND_4") (pintype "bidirectional"))
      (node (ref "U$14") (pin "5") (pinfunction "GND2_5") (pintype "bidirectional"))
      (node (ref "U$15") (pin "1") (pinfunction "GND_1") (pintype "bidirectional"))
      (node (ref "U$15") (pin "3") (pinfunction "GND2_3") (pintype "bidirectional"))
      (node (ref "U$15") (pin "4") (pinfunction "GND_4") (pintype "bidirectional"))
      (node (ref "U$15") (pin "5") (pinfunction "GND2_5") (pintype "bidirectional"))
      (node (ref "U$17") (pin "11") (pinfunction "GND_11") (pintype "bidirectional"))
      (node (ref "U$17") (pin "9") (pinfunction "VREF_9") (pintype "bidirectional"))
      (node (ref "U$19") (pin "1") (pinfunction "GND_1") (pintype "bidirectional"))
      (node (ref "U$19") (pin "3") (pinfunction "GND2_3") (pintype "bidirectional"))
      (node (ref "U$19") (pin "4") (pinfunction "GND_4") (pintype "bidirectional"))
      (node (ref "U$19") (pin "5") (pinfunction "GND2_5") (pintype "bidirectional"))
      (node (ref "U$20") (pin "1") (pinfunction "GND_1") (pintype "bidirectional"))
      (node (ref "U$20") (pin "3") (pinfunction "GND2_3") (pintype "bidirectional"))
      (node (ref "U$20") (pin "4") (pinfunction "GND_4") (pintype "bidirectional"))
      (node (ref "U$20") (pin "5") (pinfunction "GND2_5") (pintype "bidirectional"))
      (node (ref "U$22") (pin "GND") (pinfunction "GND_GND") (pintype "bidirectional"))
      (node (ref "U$3") (pin "GND") (pinfunction "GND_GND") (pintype "bidirectional"))
      (node (ref "U$4") (pin "1") (pinfunction "GND_1") (pintype "bidirectional"))
      (node (ref "U$4") (pin "3") (pinfunction "GND2_3") (pintype "bidirectional"))
      (node (ref "U$4") (pin "4") (pinfunction "GND_4") (pintype "bidirectional"))
      (node (ref "U$4") (pin "5") (pinfunction "GND2_5") (pintype "bidirectional"))
      (node (ref "U$5") (pin "1") (pinfunction "GND_1") (pintype "bidirectional"))
      (node (ref "U$5") (pin "3") (pinfunction "GND2_3") (pintype "bidirectional"))
      (node (ref "U$5") (pin "4") (pinfunction "GND_4") (pintype "bidirectional"))
      (node (ref "U$5") (pin "5") (pinfunction "GND2_5") (pintype "bidirectional"))
      (node (ref "U$7") (pin "11") (pinfunction "GND_11") (pintype "bidirectional"))
      (node (ref "U$7") (pin "9") (pinfunction "VREF_9") (pintype "bidirectional"))
      (node (ref "U$9") (pin "1") (pinfunction "GND_1") (pintype "bidirectional"))
      (node (ref "U$9") (pin "3") (pinfunction "GND2_3") (pintype "bidirectional"))
      (node (ref "U$9") (pin "4") (pinfunction "GND_4") (pintype "bidirectional"))
      (node (ref "U$9") (pin "5") (pinfunction "GND2_5") (pintype "bidirectional"))
    )
    (net (code "4") (name "Net-(C13-Pad2)") (class "Default")
      (node (ref "C13") (pin "2") (pinfunction "2_2") (pintype "passive"))
      (node (ref "R6") (pin "1") (pinfunction "1_1") (pintype "passive"))
    )
    (net (code "5") (name "Net-(C28-Pad2)") (class "Default")
      (node (ref "C28") (pin "2") (pinfunction "2_2") (pintype "passive"))
      (node (ref "R13") (pin "1") (pinfunction "1_1") (pintype "passive"))
    )
    (net (code "6") (name "Net-(C44-Pad2)") (class "Default")
      (node (ref "C44") (pin "2") (pinfunction "2_2") (pintype "passive"))
      (node (ref "R21") (pin "1") (pinfunction "1_1") (pintype "passive"))
    )
    (net (code "7") (name "Net-(C60-Pad2)") (class "Default")
      (node (ref "C60") (pin "2") (pinfunction "2_2") (pintype "passive"))
      (node (ref "R29") (pin "1") (pinfunction "1_1") (pintype "passive"))
    )
    (net (code "8") (name "Net-(C65-Pad1)") (class "Default")
      (node (ref "C65") (pin "1") (pinfunction "1_1") (pintype "passive"))
      (node (ref "R33") (pin "1") (pinfunction "1_1") (pintype "passive"))
    )
    (net (code "9") (name "Net-(C66-Pad1)") (class "Default")
      (node (ref "C66") (pin "1") (pinfunction "1_1") (pintype "passive"))
      (node (ref "R34") (pin "1") (pinfunction "1_1") (pintype "passive"))
    )
    (net (code "10") (name "Net-(C67-Pad1)") (class "Default")
      (node (ref "C67") (pin "1") (pinfunction "1_1") (pintype "passive"))
      (node (ref "R35") (pin "1") (pinfunction "1_1") (pintype "passive"))
    )
    (net (code "11") (name "Net-(C68-Pad1)") (class "Default")
      (node (ref "C68") (pin "1") (pinfunction "1_1") (pintype "passive"))
      (node (ref "R36") (pin "1") (pinfunction "1_1") (pintype "passive"))
    )
    (net (code "12") (name "Net-(IC1-+OUT)") (class "Default")
      (node (ref "C5") (pin "1") (pinfunction "1_1") (pintype "passive"))
      (node (ref "IC1") (pin "7") (pinfunction "+OUT_7") (pintype "output"))
    )
    (net (code "13") (name "Net-(IC1--OUT)") (class "Default")
      (node (ref "C4") (pin "1") (pinfunction "1_1") (pintype "passive"))
      (node (ref "IC1") (pin "6") (pinfunction "-OUT_6") (pintype "output"))
    )
    (net (code "14") (name "Net-(IC1-IN)") (class "Default")
      (node (ref "IC1") (pin "2") (pinfunction "IN_2") (pintype "input"))
      (node (ref "PD1") (pin "C") (pinfunction "C_C") (pintype "passive"))
    )
    (net (code "15") (name "Net-(IC1-VBYP)") (class "Default")
      (node (ref "C2") (pin "2") (pinfunction "2_2") (pintype "passive"))
      (node (ref "IC1") (pin "4") (pinfunction "VBYP_4") (pintype "input"))
    )
    (net (code "16") (name "Net-(IC2-+OUT)") (class "Default")
      (node (ref "C21") (pin "1") (pinfunction "1_1") (pintype "passive"))
      (node (ref "IC2") (pin "7") (pinfunction "+OUT_7") (pintype "output"))
    )
    (net (code "17") (name "Net-(IC2--OUT)") (class "Default")
      (node (ref "C20") (pin "1") (pinfunction "1_1") (pintype "passive"))
      (node (ref "IC2") (pin "6") (pinfunction "-OUT_6") (pintype "output"))
    )
    (net (code "18") (name "Net-(IC2-IN)") (class "Default")
      (node (ref "IC2") (pin "2") (pinfunction "IN_2") (pintype "input"))
      (node (ref "PD2") (pin "C") (pinfunction "C_C") (pintype "passive"))
    )
    (net (code "19") (name "Net-(IC2-VBYP)") (class "Default")
      (node (ref "C18") (pin "2") (pinfunction "2_2") (pintype "passive"))
      (node (ref "IC2") (pin "4") (pinfunction "VBYP_4") (pintype "input"))
    )
    (net (code "20") (name "Net-(IC3-+OUT)") (class "Default")
      (node (ref "C37") (pin "1") (pinfunction "1_1") (pintype "passive"))
      (node (ref "IC3") (pin "7") (pinfunction "+OUT_7") (pintype "output"))
    )
    (net (code "21") (name "Net-(IC3--OUT)") (class "Default")
      (node (ref "C36") (pin "1") (pinfunction "1_1") (pintype "passive"))
      (node (ref "IC3") (pin "6") (pinfunction "-OUT_6") (pintype "output"))
    )
    (net (code "22") (name "Net-(IC3-IN)") (class "Default")
      (node (ref "IC3") (pin "2") (pinfunction "IN_2") (pintype "input"))
      (node (ref "PD3") (pin "C") (pinfunction "C_C") (pintype "passive"))
    )
    (net (code "23") (name "Net-(IC3-VBYP)") (class "Default")
      (node (ref "C34") (pin "2") (pinfunction "2_2") (pintype "passive"))
      (node (ref "IC3") (pin "4") (pinfunction "VBYP_4") (pintype "input"))
    )
    (net (code "24") (name "Net-(IC4-+OUT)") (class "Default")
      (node (ref "C53") (pin "1") (pinfunction "1_1") (pintype "passive"))
      (node (ref "IC4") (pin "7") (pinfunction "+OUT_7") (pintype "output"))
    )
    (net (code "25") (name "Net-(IC4--OUT)") (class "Default")
      (node (ref "C52") (pin "1") (pinfunction "1_1") (pintype "passive"))
      (node (ref "IC4") (pin "6") (pinfunction "-OUT_6") (pintype "output"))
    )
    (net (code "26") (name "Net-(IC4-IN)") (class "Default")
      (node (ref "IC4") (pin "2") (pinfunction "IN_2") (pintype "input"))
      (node (ref "PD4") (pin "C") (pinfunction "C_C") (pintype "passive"))
    )
    (net (code "27") (name "Net-(IC4-VBYP)") (class "Default")
      (node (ref "C50") (pin "2") (pinfunction "2_2") (pintype "passive"))
      (node (ref "IC4") (pin "4") (pinfunction "VBYP_4") (pintype "input"))
    )
    (net (code "28") (name "Net-(U$1-+RG)") (class "Default")
      (node (ref "R3") (pin "1") (pinfunction "1_1") (pintype "passive"))
      (node (ref "U$1") (pin "4") (pinfunction "+RG_4") (pintype "bidirectional"))
    )
    (net (code "29") (name "Net-(U$1-+VIN)") (class "Default")
      (node (ref "C5") (pin "2") (pinfunction "2_2") (pintype "passive"))
      (node (ref "R1") (pin "1") (pinfunction "1_1") (pintype "passive"))
      (node (ref "U$1") (pin "3") (pinfunction "+VIN_3") (pintype "bidirectional"))
    )
    (net (code "30") (name "Net-(U$1--RG)") (class "Default")
      (node (ref "R3") (pin "2") (pinfunction "2_2") (pintype "passive"))
      (node (ref "U$1") (pin "5") (pinfunction "-RG_5") (pintype "bidirectional"))
    )
    (net (code "31") (name "Net-(U$1--VIN)") (class "Default")
      (node (ref "C4") (pin "2") (pinfunction "2_2") (pintype "passive"))
      (node (ref "R2") (pin "2") (pinfunction "2_2") (pintype "passive"))
      (node (ref "U$1") (pin "6") (pinfunction "-VIN_6") (pintype "bidirectional"))
    )
    (net (code "32") (name "Net-(U$1-I-)") (class "Default")
      (node (ref "R4") (pin "1") (pinfunction "1_1") (pintype "passive"))
      (node (ref "U$1") (pin "12") (pinfunction "I-_12") (pintype "bidirectional"))
    )
    (net (code "33") (name "Net-(U$1-VG)") (class "Default")
      (node (ref "U$1") (pin "2") (pinfunction "VG_2") (pintype "bidirectional"))
      (node (ref "U$2") (pin "2") (pinfunction "2_2") (pintype "bidirectional"))
      (node (ref "U$4") (pin "2") (pinfunction "SIGNAL_2") (pintype "bidirectional"))
    )
    (net (code "34") (name "Net-(U$1-VOUT)") (class "Default")
      (node (ref "C13") (pin "1") (pinfunction "1_1") (pintype "passive"))
      (node (ref "R33") (pin "2") (pinfunction "2_2") (pintype "passive"))
      (node (ref "R4") (pin "2") (pinfunction "2_2") (pintype "passive"))
      (node (ref "U$1") (pin "10") (pinfunction "VOUT_10") (pintype "bidirectional"))
    )
    (net (code "35") (name "Net-(U$5-SIGNAL)") (class "Default")
      (node (ref "R8") (pin "2") (pinfunction "2_2") (pintype "passive"))
      (node (ref "U$5") (pin "2") (pinfunction "SIGNAL_2") (pintype "bidirectional"))
    )
    (net (code "36") (name "Net-(U$6-+IN)") (class "Default")
      (node (ref "R7") (pin "1") (pinfunction "1_1") (pintype "passive"))
      (node (ref "U$6") (pin "3") (pinfunction "+IN_3") (pintype "bidirectional"))
    )
    (net (code "37") (name "Net-(U$6--IN)") (class "Default")
      (node (ref "R5") (pin "1") (pinfunction "1_1") (pintype "passive"))
      (node (ref "R6") (pin "2") (pinfunction "2_2") (pintype "passive"))
      (node (ref "U$6") (pin "4") (pinfunction "-IN_4") (pintype "bidirectional"))
    )
    (net (code "38") (name "Net-(U$6-OUT)") (class "Default")
      (node (ref "R5") (pin "2") (pinfunction "2_2") (pintype "passive"))
      (node (ref "R8") (pin "1") (pinfunction "1_1") (pintype "passive"))
      (node (ref "U$6") (pin "1") (pinfunction "OUT_1") (pintype "bidirectional"))
    )
    (net (code "39") (name "Net-(U$7-+RG)") (class "Default")
      (node (ref "R11") (pin "1") (pinfunction "1_1") (pintype "passive"))
      (node (ref "U$7") (pin "4") (pinfunction "+RG_4") (pintype "bidirectional"))
    )
    (net (code "40") (name "Net-(U$7-+VIN)") (class "Default")
      (node (ref "C21") (pin "2") (pinfunction "2_2") (pintype "passive"))
      (node (ref "R9") (pin "1") (pinfunction "1_1") (pintype "passive"))
      (node (ref "U$7") (pin "3") (pinfunction "+VIN_3") (pintype "bidirectional"))
    )
    (net (code "41") (name "Net-(U$7--RG)") (class "Default")
      (node (ref "R11") (pin "2") (pinfunction "2_2") (pintype "passive"))
      (node (ref "U$7") (pin "5") (pinfunction "-RG_5") (pintype "bidirectional"))
    )
    (net (code "42") (name "Net-(U$7--VIN)") (class "Default")
      (node (ref "C20") (pin "2") (pinfunction "2_2") (pintype "passive"))
      (node (ref "R10") (pin "2") (pinfunction "2_2") (pintype "passive"))
      (node (ref "U$7") (pin "6") (pinfunction "-VIN_6") (pintype "bidirectional"))
    )
    (net (code "43") (name "Net-(U$7-I-)") (class "Default")
      (node (ref "R12") (pin "1") (pinfunction "1_1") (pintype "passive"))
      (node (ref "U$7") (pin "12") (pinfunction "I-_12") (pintype "bidirectional"))
    )
    (net (code "44") (name "Net-(U$7-VG)") (class "Default")
      (node (ref "U$7") (pin "2") (pinfunction "VG_2") (pintype "bidirectional"))
      (node (ref "U$8") (pin "2") (pinfunction "2_2") (pintype "bidirectional"))
      (node (ref "U$9") (pin "2") (pinfunction "SIGNAL_2") (pintype "bidirectional"))
    )
    (net (code "45") (name "Net-(U$7-VOUT)") (class "Default")
      (node (ref "C28") (pin "1") (pinfunction "1_1") (pintype "passive"))
      (node (ref "R12") (pin "2") (pinfunction "2_2") (pintype "passive"))
      (node (ref "R36") (pin "2") (pinfunction "2_2") (pintype "passive"))
      (node (ref "U$7") (pin "10") (pinfunction "VOUT_10") (pintype "bidirectional"))
    )
    (net (code "46") (name "Net-(U$10-SIGNAL)") (class "Default")
      (node (ref "R16") (pin "2") (pinfunction "2_2") (pintype "passive"))
      (node (ref "U$10") (pin "2") (pinfunction "SIGNAL_2") (pintype "bidirectional"))
    )
    (net (code "47") (name "Net-(U$11-+IN)") (class "Default")
      (node (ref "R15") (pin "1") (pinfunction "1_1") (pintype "passive"))
      (node (ref "U$11") (pin "3") (pinfunction "+IN_3") (pintype "bidirectional"))
    )
    (net (code "48") (name "Net-(U$11--IN)") (class "Default")
      (node (ref "R13") (pin "2") (pinfunction "2_2") (pintype "passive"))
      (node (ref "R14") (pin "1") (pinfunction "1_1") (pintype "passive"))
      (node (ref "U$11") (pin "4") (pinfunction "-IN_4") (pintype "bidirectional"))
    )
    (net (code "49") (name "Net-(U$11-OUT)") (class "Default")
      (node (ref "R14") (pin "2") (pinfunction "2_2") (pintype "passive"))
      (node (ref "R16") (pin "1") (pinfunction "1_1") (pintype "passive"))
      (node (ref "U$11") (pin "1") (pinfunction "OUT_1") (pintype "bidirectional"))
    )
    (net (code "50") (name "Net-(U$12-+RG)") (class "Default")
      (node (ref "R19") (pin "1") (pinfunction "1_1") (pintype "passive"))
      (node (ref "U$12") (pin "4") (pinfunction "+RG_4") (pintype "bidirectional"))
    )
    (net (code "51") (name "Net-(U$12-+VIN)") (class "Default")
      (node (ref "C37") (pin "2") (pinfunction "2_2") (pintype "passive"))
      (node (ref "R17") (pin "1") (pinfunction "1_1") (pintype "passive"))
      (node (ref "U$12") (pin "3") (pinfunction "+VIN_3") (pintype "bidirectional"))
    )
    (net (code "52") (name "Net-(U$12--RG)") (class "Default")
      (node (ref "R19") (pin "2") (pinfunction "2_2") (pintype "passive"))
      (node (ref "U$12") (pin "5") (pinfunction "-RG_5") (pintype "bidirectional"))
    )
    (net (code "53") (name "Net-(U$12--VIN)") (class "Default")
      (node (ref "C36") (pin "2") (pinfunction "2_2") (pintype "passive"))
      (node (ref "R18") (pin "2") (pinfunction "2_2") (pintype "passive"))
      (node (ref "U$12") (pin "6") (pinfunction "-VIN_6") (pintype "bidirectional"))
    )
    (net (code "54") (name "Net-(U$12-I-)") (class "Default")
      (node (ref "R20") (pin "1") (pinfunction "1_1") (pintype "passive"))
      (node (ref "U$12") (pin "12") (pinfunction "I-_12") (pintype "bidirectional"))
    )
    (net (code "55") (name "Net-(U$12-VG)") (class "Default")
      (node (ref "U$12") (pin "2") (pinfunction "VG_2") (pintype "bidirectional"))
      (node (ref "U$13") (pin "2") (pinfunction "2_2") (pintype "bidirectional"))
      (node (ref "U$14") (pin "2") (pinfunction "SIGNAL_2") (pintype "bidirectional"))
    )
    (net (code "56") (name "Net-(U$12-VOUT)") (class "Default")
      (node (ref "C44") (pin "1") (pinfunction "1_1") (pintype "passive"))
      (node (ref "R20") (pin "2") (pinfunction "2_2") (pintype "passive"))
      (node (ref "R35") (pin "2") (pinfunction "2_2") (pintype "passive"))
      (node (ref "U$12") (pin "10") (pinfunction "VOUT_10") (pintype "bidirectional"))
    )
    (net (code "57") (name "Net-(U$15-SIGNAL)") (class "Default")
      (node (ref "R24") (pin "2") (pinfunction "2_2") (pintype "passive"))
      (node (ref "U$15") (pin "2") (pinfunction "SIGNAL_2") (pintype "bidirectional"))
    )
    (net (code "58") (name "Net-(U$16-+IN)") (class "Default")
      (node (ref "R23") (pin "1") (pinfunction "1_1") (pintype "passive"))
      (node (ref "U$16") (pin "3") (pinfunction "+IN_3") (pintype "bidirectional"))
    )
    (net (code "59") (name "Net-(U$16--IN)") (class "Default")
      (node (ref "R21") (pin "2") (pinfunction "2_2") (pintype "passive"))
      (node (ref "R22") (pin "1") (pinfunction "1_1") (pintype "passive"))
      (node (ref "U$16") (pin "4") (pinfunction "-IN_4") (pintype "bidirectional"))
    )
    (net (code "60") (name "Net-(U$16-OUT)") (class "Default")
      (node (ref "R22") (pin "2") (pinfunction "2_2") (pintype "passive"))
      (node (ref "R24") (pin "1") (pinfunction "1_1") (pintype "passive"))
      (node (ref "U$16") (pin "1") (pinfunction "OUT_1") (pintype "bidirectional"))
    )
    (net (code "61") (name "Net-(U$17-+RG)") (class "Default")
      (node (ref "R27") (pin "1") (pinfunction "1_1") (pintype "passive"))
      (node (ref "U$17") (pin "4") (pinfunction "+RG_4") (pintype "bidirectional"))
    )
    (net (code "62") (name "Net-(U$17-+VIN)") (class "Default")
      (node (ref "C53") (pin "2") (pinfunction "2_2") (pintype "passive"))
      (node (ref "R25") (pin "1") (pinfunction "1_1") (pintype "passive"))
      (node (ref "U$17") (pin "3") (pinfunction "+VIN_3") (pintype "bidirectional"))
    )
    (net (code "63") (name "Net-(U$17--RG)") (class "Default")
      (node (ref "R27") (pin "2") (pinfunction "2_2") (pintype "passive"))
      (node (ref "U$17") (pin "5") (pinfunction "-RG_5") (pintype "bidirectional"))
    )
    (net (code "64") (name "Net-(U$17--VIN)") (class "Default")
      (node (ref "C52") (pin "2") (pinfunction "2_2") (pintype "passive"))
      (node (ref "R26") (pin "2") (pinfunction "2_2") (pintype "passive"))
      (node (ref "U$17") (pin "6") (pinfunction "-VIN_6") (pintype "bidirectional"))
    )
    (net (code "65") (name "Net-(U$17-I-)") (class "Default")
      (node (ref "R28") (pin "1") (pinfunction "1_1") (pintype "passive"))
      (node (ref "U$17") (pin "12") (pinfunction "I-_12") (pintype "bidirectional"))
    )
    (net (code "66") (name "Net-(U$17-VG)") (class "Default")
      (node (ref "U$17") (pin "2") (pinfunction "VG_2") (pintype "bidirectional"))
      (node (ref "U$18") (pin "2") (pinfunction "2_2") (pintype "bidirectional"))
      (node (ref "U$19") (pin "2") (pinfunction "SIGNAL_2") (pintype "bidirectional"))
    )
    (net (code "67") (name "Net-(U$17-VOUT)") (class "Default")
      (node (ref "C60") (pin "1") (pinfunction "1_1") (pintype "passive"))
      (node (ref "R28") (pin "2") (pinfunction "2_2") (pintype "passive"))
      (node (ref "R34") (pin "2") (pinfunction "2_2") (pintype "passive"))
      (node (ref "U$17") (pin "10") (pinfunction "VOUT_10") (pintype "bidirectional"))
    )
    (net (code "68") (name "Net-(U$20-SIGNAL)") (class "Default")
      (node (ref "R32") (pin "2") (pinfunction "2_2") (pintype "passive"))
      (node (ref "U$20") (pin "2") (pinfunction "SIGNAL_2") (pintype "bidirectional"))
    )
    (net (code "69") (name "Net-(U$21-+IN)") (class "Default")
      (node (ref "R31") (pin "1") (pinfunction "1_1") (pintype "passive"))
      (node (ref "U$21") (pin "3") (pinfunction "+IN_3") (pintype "bidirectional"))
    )
    (net (code "70") (name "Net-(U$21--IN)") (class "Default")
      (node (ref "R29") (pin "2") (pinfunction "2_2") (pintype "passive"))
      (node (ref "R30") (pin "1") (pinfunction "1_1") (pintype "passive"))
      (node (ref "U$21") (pin "4") (pinfunction "-IN_4") (pintype "bidirectional"))
    )
    (net (code "71") (name "Net-(U$21-OUT)") (class "Default")
      (node (ref "R30") (pin "2") (pinfunction "2_2") (pintype "passive"))
      (node (ref "R32") (pin "1") (pinfunction "1_1") (pintype "passive"))
      (node (ref "U$21") (pin "1") (pinfunction "OUT_1") (pintype "bidirectional"))
    )
  )
)
